# Down_Linker_IM.net
KiCad netlist of a schematic drawn in EAGLE
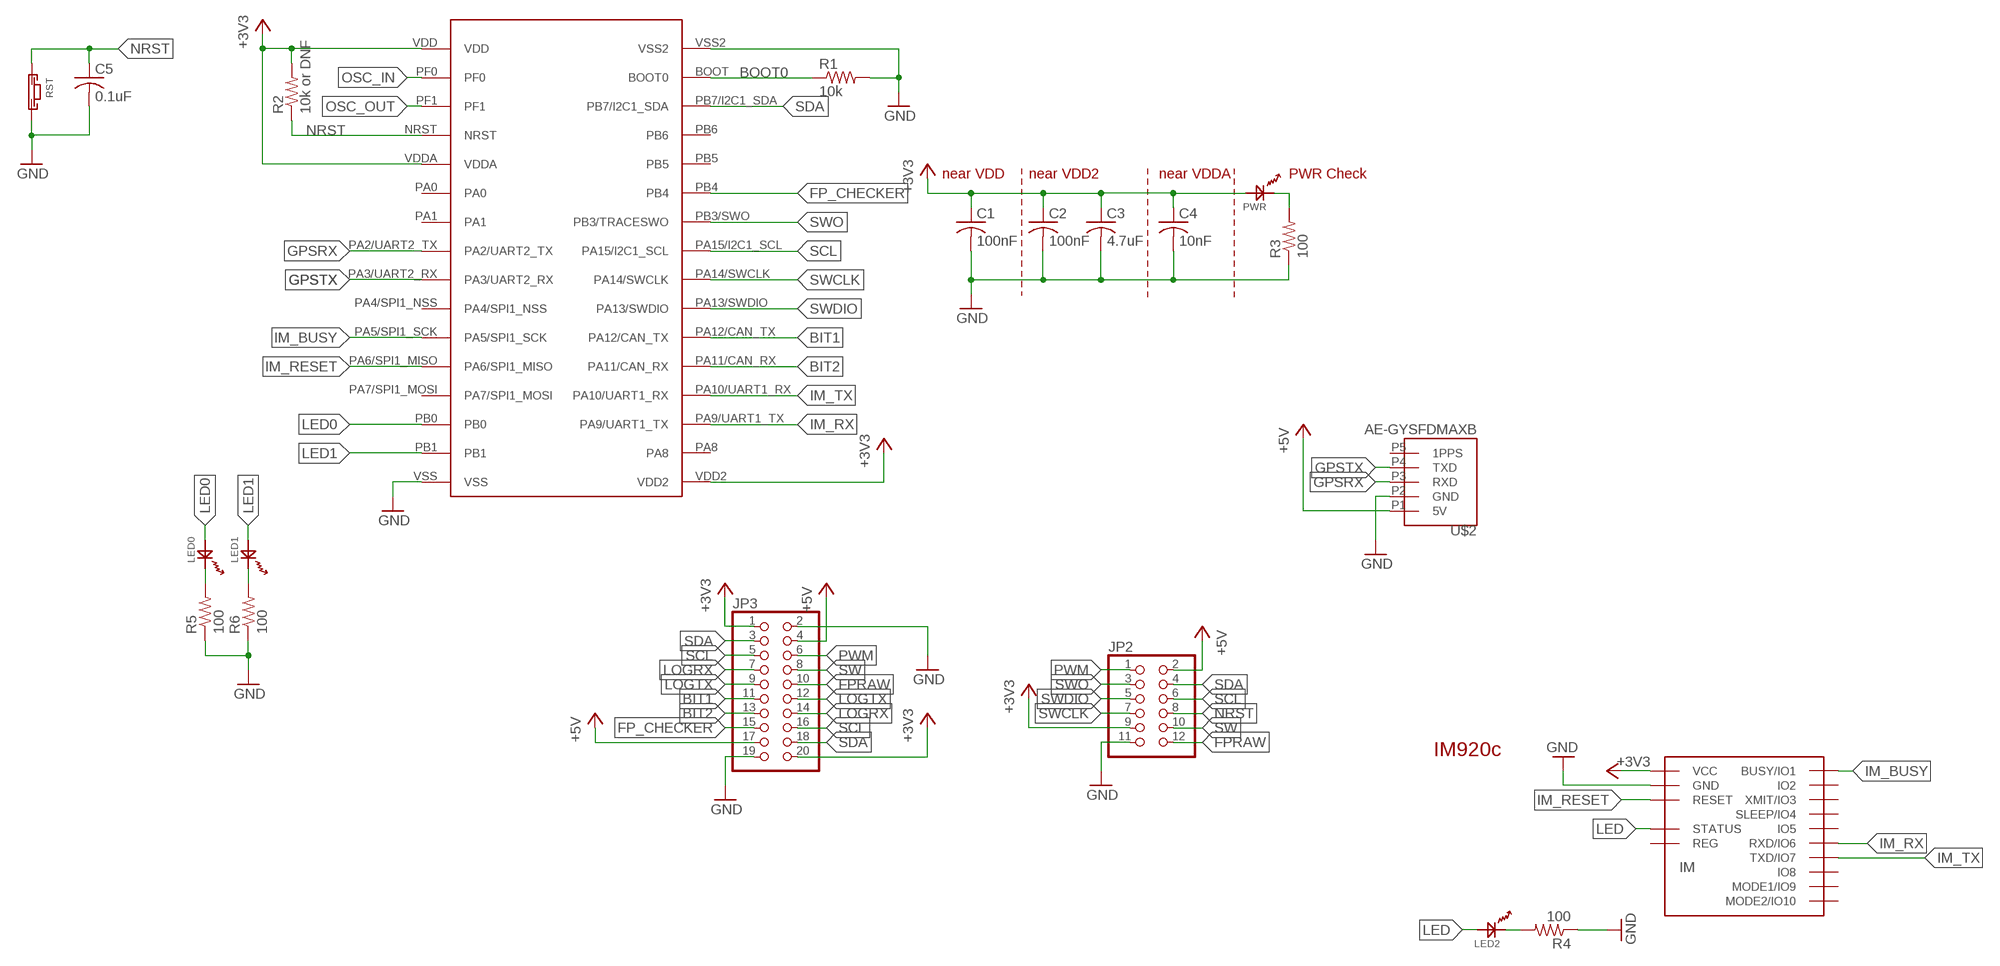
[diagram p0: schematic, sheet 1]

(export (version "E")
  (design (tool "Eeschema 10.0.6"))
  (components
    (comp (ref "C1")
      (value "100nF")
      (footprint "eagle-import:C1608")
      (libsource (lib "eagle-import") (part "C-USC1608"))
    )
    (comp (ref "C2")
      (value "100nF")
      (footprint "eagle-import:C1608")
      (libsource (lib "eagle-import") (part "C-USC1608"))
    )
    (comp (ref "C3")
      (value "4.7uF")
      (footprint "eagle-import:C1608")
      (libsource (lib "eagle-import") (part "C-USC1608"))
    )
    (comp (ref "C4")
      (value "10nF")
      (footprint "eagle-import:C1608")
      (libsource (lib "eagle-import") (part "C-USC1608"))
    )
    (comp (ref "C5")
      (value "0.1uF")
      (footprint "eagle-import:C1608")
      (libsource (lib "eagle-import") (part "C-USC1608"))
    )
    (comp (ref "IM")
      (value "IM920C")
      (footprint "eagle-import:IM920C")
      (libsource (lib "eagle-import") (part "IM920C"))
    )
    (comp (ref "JP2")
      (value "PINHD-2X6/90")
      (footprint "eagle-import:2X06_90")
      (libsource (lib "eagle-import") (part "PINHD-2X6/90"))
    )
    (comp (ref "JP3")
      (value "PINHD-2X10/90")
      (footprint "eagle-import:2X10_90")
      (libsource (lib "eagle-import") (part "PINHD-2X10/90"))
    )
    (comp (ref "LED0")
      (value "OSXX1608C1A")
      (footprint "eagle-import:OSXX1608C1A")
      (libsource (lib "eagle-import") (part "OSXX1608C1A"))
    )
    (comp (ref "LED1")
      (value "OSXX1608C1A")
      (footprint "eagle-import:OSXX1608C1A")
      (libsource (lib "eagle-import") (part "OSXX1608C1A"))
    )
    (comp (ref "LED2")
      (value "OSXX1608C1A")
      (footprint "eagle-import:OSXX1608C1A")
      (libsource (lib "eagle-import") (part "OSXX1608C1A"))
    )
    (comp (ref "PWR")
      (value "OSXX1608C1A")
      (footprint "eagle-import:OSXX1608C1A")
      (libsource (lib "eagle-import") (part "OSXX1608C1A"))
    )
    (comp (ref "R1")
      (value "10k")
      (footprint "eagle-import:R0603")
      (libsource (lib "eagle-import") (part "R-US_R0603"))
    )
    (comp (ref "R2")
      (value "10k or DNF")
      (footprint "eagle-import:R0603")
      (libsource (lib "eagle-import") (part "R-US_R0603"))
    )
    (comp (ref "R3")
      (value "100")
      (footprint "eagle-import:R0603")
      (libsource (lib "eagle-import") (part "R-US_R0603"))
    )
    (comp (ref "R4")
      (value "100")
      (footprint "eagle-import:R0603")
      (libsource (lib "eagle-import") (part "R-US_R0603"))
    )
    (comp (ref "R5")
      (value "100")
      (footprint "eagle-import:R0603")
      (libsource (lib "eagle-import") (part "R-US_R0603"))
    )
    (comp (ref "R6")
      (value "100")
      (footprint "eagle-import:R0603")
      (libsource (lib "eagle-import") (part "R-US_R0603"))
    )
    (comp (ref "RST")
      (value "TVAF06-A020B-R")
      (footprint "eagle-import:TVAF06-A020B-R")
      (libsource (lib "eagle-import") (part "TVAF06-A020B-R"))
    )
    (comp (ref "U$1")
      (value "STM32F303K8")
      (footprint "eagle-import:STM32F303K8")
      (libsource (lib "eagle-import") (part "STM32F303K8"))
    )
    (comp (ref "U$2")
      (value "AE-GYSFDMAXB")
      (footprint "eagle-import:AE-GYSFDMAXB")
      (libsource (lib "eagle-import") (part "AE-GYSFDMAXB"))
    )
  )
  (nets
    (net (code "1") (name "+3V3") (class "Default")
      (node (ref "C1") (pin "1") (pinfunction "1_1") (pintype "passive"))
      (node (ref "C2") (pin "1") (pinfunction "1_1") (pintype "passive"))
      (node (ref "C3") (pin "1") (pinfunction "1_1") (pintype "passive"))
      (node (ref "C4") (pin "1") (pinfunction "1_1") (pintype "passive"))
      (node (ref "IM") (pin "$P17") (pinfunction "VCC_$P17") (pintype "bidirectional"))
      (node (ref "JP2") (pin "9") (pinfunction "9_9") (pintype "passive"))
      (node (ref "JP3") (pin "1") (pinfunction "1_1") (pintype "passive"))
      (node (ref "JP3") (pin "20") (pinfunction "20_20") (pintype "passive"))
      (node (ref "PWR") (pin "AN") (pinfunction "AN_AN") (pintype "bidirectional"))
      (node (ref "R2") (pin "2") (pinfunction "2_2") (pintype "passive"))
      (node (ref "U$1") (pin "VDD") (pinfunction "VDD_VDD") (pintype "power_in"))
      (node (ref "U$1") (pin "VDD2") (pinfunction "VDD2_VDD2") (pintype "power_in"))
      (node (ref "U$1") (pin "VDDA") (pinfunction "VDDA_VDDA") (pintype "power_in"))
    )
    (net (code "2") (name "+5V") (class "Default")
      (node (ref "JP2") (pin "2") (pinfunction "2_2") (pintype "passive"))
      (node (ref "JP3") (pin "17") (pinfunction "17_17") (pintype "passive"))
      (node (ref "JP3") (pin "4") (pinfunction "4_4") (pintype "passive"))
      (node (ref "U$2") (pin "P1") (pinfunction "5V_P1") (pintype "bidirectional"))
    )
    (net (code "3") (name "/BOOT0") (class "Default")
      (node (ref "R1") (pin "1") (pinfunction "1_1") (pintype "passive"))
      (node (ref "U$1") (pin "BOOT") (pinfunction "BOOT0_BOOT") (pintype "bidirectional"))
    )
    (net (code "4") (name "BIT1") (class "Default")
      (node (ref "JP3") (pin "11") (pinfunction "11_11") (pintype "passive"))
      (node (ref "U$1") (pin "PA12/CAN_TX") (pinfunction "PA12/CAN_TX_PA12/CAN_TX") (pintype "bidirectional"))
    )
    (net (code "5") (name "BIT2") (class "Default")
      (node (ref "JP3") (pin "13") (pinfunction "13_13") (pintype "passive"))
      (node (ref "U$1") (pin "PA11/CAN_RX") (pinfunction "PA11/CAN_RX_PA11/CAN_RX") (pintype "bidirectional"))
    )
    (net (code "6") (name "FPRAW") (class "Default")
      (node (ref "JP2") (pin "12") (pinfunction "12_12") (pintype "passive"))
      (node (ref "JP3") (pin "10") (pinfunction "10_10") (pintype "passive"))
    )
    (net (code "7") (name "FP_CHECKER") (class "Default")
      (node (ref "JP3") (pin "15") (pinfunction "15_15") (pintype "passive"))
      (node (ref "U$1") (pin "PB4") (pinfunction "PB4_PB4") (pintype "bidirectional"))
    )
    (net (code "8") (name "GND") (class "Default")
      (node (ref "C1") (pin "2") (pinfunction "2_2") (pintype "passive"))
      (node (ref "C2") (pin "2") (pinfunction "2_2") (pintype "passive"))
      (node (ref "C3") (pin "2") (pinfunction "2_2") (pintype "passive"))
      (node (ref "C4") (pin "2") (pinfunction "2_2") (pintype "passive"))
      (node (ref "C5") (pin "2") (pinfunction "2_2") (pintype "passive"))
      (node (ref "IM") (pin "$P18") (pinfunction "GND_$P18") (pintype "bidirectional"))
      (node (ref "JP2") (pin "11") (pinfunction "11_11") (pintype "passive"))
      (node (ref "JP3") (pin "19") (pinfunction "19_19") (pintype "passive"))
      (node (ref "JP3") (pin "2") (pinfunction "2_2") (pintype "passive"))
      (node (ref "R1") (pin "2") (pinfunction "2_2") (pintype "passive"))
      (node (ref "R3") (pin "1") (pinfunction "1_1") (pintype "passive"))
      (node (ref "R4") (pin "1") (pinfunction "1_1") (pintype "passive"))
      (node (ref "R5") (pin "1") (pinfunction "1_1") (pintype "passive"))
      (node (ref "R6") (pin "1") (pinfunction "1_1") (pintype "passive"))
      (node (ref "RST") (pin "P$2") (pinfunction "P$2_P$2") (pintype "bidirectional"))
      (node (ref "U$1") (pin "VSS") (pinfunction "VSS_VSS") (pintype "power_in"))
      (node (ref "U$1") (pin "VSS2") (pinfunction "VSS2_VSS2") (pintype "power_in"))
      (node (ref "U$2") (pin "P2") (pinfunction "GND_P2") (pintype "bidirectional"))
    )
    (net (code "9") (name "GPSRX") (class "Default")
      (node (ref "U$1") (pin "PA2/UART2_TX") (pinfunction "PA2/UART2_TX_PA2/UART2_TX") (pintype "bidirectional"))
      (node (ref "U$2") (pin "P3") (pinfunction "RXD_P3") (pintype "bidirectional"))
    )
    (net (code "10") (name "GPSTX") (class "Default")
      (node (ref "U$1") (pin "PA3/UART2_RX") (pinfunction "PA3/UART2_RX_PA3/UART2_RX") (pintype "bidirectional"))
      (node (ref "U$2") (pin "P4") (pinfunction "TXD_P4") (pintype "bidirectional"))
    )
    (net (code "11") (name "IM_BUSY") (class "Default")
      (node (ref "IM") (pin "$P1") (pinfunction "BUSY/IO1_$P1") (pintype "bidirectional"))
      (node (ref "U$1") (pin "PA5/SPI1_SCK") (pinfunction "PA5/SPI1_SCK_PA5/SPI1_SCK") (pintype "bidirectional"))
    )
    (net (code "12") (name "IM_RESET") (class "Default")
      (node (ref "IM") (pin "$P19") (pinfunction "RESET_$P19") (pintype "bidirectional"))
      (node (ref "U$1") (pin "PA6/SPI1_MISO") (pinfunction "PA6/SPI1_MISO_PA6/SPI1_MISO") (pintype "bidirectional"))
    )
    (net (code "13") (name "IM_RX") (class "Default")
      (node (ref "IM") (pin "$P6") (pinfunction "RXD/IO6_$P6") (pintype "bidirectional"))
      (node (ref "U$1") (pin "PA9/UART1_TX") (pinfunction "PA9/UART1_TX_PA9/UART1_TX") (pintype "bidirectional"))
    )
    (net (code "14") (name "IM_TX") (class "Default")
      (node (ref "IM") (pin "$P7") (pinfunction "TXD/IO7_$P7") (pintype "bidirectional"))
      (node (ref "U$1") (pin "PA10/UART1_RX") (pinfunction "PA10/UART1_RX_PA10/UART1_RX") (pintype "bidirectional"))
    )
    (net (code "15") (name "LED") (class "Default")
      (node (ref "IM") (pin "$P15") (pinfunction "STATUS_$P15") (pintype "bidirectional"))
      (node (ref "LED2") (pin "AN") (pinfunction "AN_AN") (pintype "bidirectional"))
    )
    (net (code "16") (name "LED0") (class "Default")
      (node (ref "LED0") (pin "AN") (pinfunction "AN_AN") (pintype "bidirectional"))
      (node (ref "U$1") (pin "PB0") (pinfunction "PB0_PB0") (pintype "bidirectional"))
    )
    (net (code "17") (name "LED1") (class "Default")
      (node (ref "LED1") (pin "AN") (pinfunction "AN_AN") (pintype "bidirectional"))
      (node (ref "U$1") (pin "PB1") (pinfunction "PB1_PB1") (pintype "bidirectional"))
    )
    (net (code "18") (name "LOGRX") (class "Default")
      (node (ref "JP3") (pin "14") (pinfunction "14_14") (pintype "passive"))
      (node (ref "JP3") (pin "7") (pinfunction "7_7") (pintype "passive"))
    )
    (net (code "19") (name "LOGTX") (class "Default")
      (node (ref "JP3") (pin "12") (pinfunction "12_12") (pintype "passive"))
      (node (ref "JP3") (pin "9") (pinfunction "9_9") (pintype "passive"))
    )
    (net (code "20") (name "NRST") (class "Default")
      (node (ref "C5") (pin "1") (pinfunction "1_1") (pintype "passive"))
      (node (ref "JP2") (pin "8") (pinfunction "8_8") (pintype "passive"))
      (node (ref "R2") (pin "1") (pinfunction "1_1") (pintype "passive"))
      (node (ref "RST") (pin "P$1") (pinfunction "P$1_P$1") (pintype "bidirectional"))
      (node (ref "U$1") (pin "NRST") (pinfunction "NRST_NRST") (pintype "bidirectional"))
    )
    (net (code "21") (name "Net-(LED0-PadCT)") (class "Default")
      (node (ref "LED0") (pin "CT") (pinfunction "CT_CT") (pintype "bidirectional"))
      (node (ref "R5") (pin "2") (pinfunction "2_2") (pintype "passive"))
    )
    (net (code "22") (name "Net-(LED1-PadCT)") (class "Default")
      (node (ref "LED1") (pin "CT") (pinfunction "CT_CT") (pintype "bidirectional"))
      (node (ref "R6") (pin "2") (pinfunction "2_2") (pintype "passive"))
    )
    (net (code "23") (name "Net-(LED2-PadCT)") (class "Default")
      (node (ref "LED2") (pin "CT") (pinfunction "CT_CT") (pintype "bidirectional"))
      (node (ref "R4") (pin "2") (pinfunction "2_2") (pintype "passive"))
    )
    (net (code "24") (name "Net-(PWR-PadCT)") (class "Default")
      (node (ref "PWR") (pin "CT") (pinfunction "CT_CT") (pintype "bidirectional"))
      (node (ref "R3") (pin "2") (pinfunction "2_2") (pintype "passive"))
    )
    (net (code "25") (name "OSC_IN") (class "Default")
      (node (ref "U$1") (pin "PF0") (pinfunction "PF0_PF0") (pintype "bidirectional"))
    )
    (net (code "26") (name "OSC_OUT") (class "Default")
      (node (ref "U$1") (pin "PF1") (pinfunction "PF1_PF1") (pintype "bidirectional"))
    )
    (net (code "27") (name "PWM") (class "Default")
      (node (ref "JP2") (pin "1") (pinfunction "1_1") (pintype "passive"))
      (node (ref "JP3") (pin "6") (pinfunction "6_6") (pintype "passive"))
    )
    (net (code "28") (name "SCL") (class "Default")
      (node (ref "JP2") (pin "6") (pinfunction "6_6") (pintype "passive"))
      (node (ref "JP3") (pin "16") (pinfunction "16_16") (pintype "passive"))
      (node (ref "JP3") (pin "5") (pinfunction "5_5") (pintype "passive"))
      (node (ref "U$1") (pin "PA15/I2C1_SCL") (pinfunction "PA15/I2C1_SCL_PA15/I2C1_SCL") (pintype "bidirectional"))
    )
    (net (code "29") (name "SDA") (class "Default")
      (node (ref "JP2") (pin "4") (pinfunction "4_4") (pintype "passive"))
      (node (ref "JP3") (pin "18") (pinfunction "18_18") (pintype "passive"))
      (node (ref "JP3") (pin "3") (pinfunction "3_3") (pintype "passive"))
      (node (ref "U$1") (pin "PB7/I2C1_SDA") (pinfunction "PB7/I2C1_SDA_PB7/I2C1_SDA") (pintype "bidirectional"))
    )
    (net (code "30") (name "SW") (class "Default")
      (node (ref "JP2") (pin "10") (pinfunction "10_10") (pintype "passive"))
      (node (ref "JP3") (pin "8") (pinfunction "8_8") (pintype "passive"))
    )
    (net (code "31") (name "SWCLK") (class "Default")
      (node (ref "JP2") (pin "7") (pinfunction "7_7") (pintype "passive"))
      (node (ref "U$1") (pin "PA14/SWCLK") (pinfunction "PA14/SWCLK_PA14/SWCLK") (pintype "bidirectional"))
    )
    (net (code "32") (name "SWDIO") (class "Default")
      (node (ref "JP2") (pin "5") (pinfunction "5_5") (pintype "passive"))
      (node (ref "U$1") (pin "PA13/SWDIO") (pinfunction "PA13/SWDIO_PA13/SWDIO") (pintype "bidirectional"))
    )
    (net (code "33") (name "SWO") (class "Default")
      (node (ref "JP2") (pin "3") (pinfunction "3_3") (pintype "passive"))
      (node (ref "U$1") (pin "PB3/SWO") (pinfunction "PB3/TRACESWO_PB3/SWO") (pintype "bidirectional"))
    )
    (net (code "34") (name "unconnected-(IM-IO2-Pad$P2)") (class "Default")
      (node (ref "IM") (pin "$P2") (pinfunction "IO2_$P2") (pintype "bidirectional"))
    )
    (net (code "35") (name "unconnected-(IM-IO5-Pad$P5)") (class "Default")
      (node (ref "IM") (pin "$P5") (pinfunction "IO5_$P5") (pintype "bidirectional"))
    )
    (net (code "36") (name "unconnected-(IM-IO8-Pad$P8)") (class "Default")
      (node (ref "IM") (pin "$P8") (pinfunction "IO8_$P8") (pintype "bidirectional"))
    )
    (net (code "37") (name "unconnected-(IM-MODE1{slash}IO9-Pad$P9)") (class "Default")
      (node (ref "IM") (pin "$P9") (pinfunction "MODE1/IO9_$P9") (pintype "bidirectional"))
    )
    (net (code "38") (name "unconnected-(IM-MODE2{slash}IO10-Pad$P10)") (class "Default")
      (node (ref "IM") (pin "$P10") (pinfunction "MODE2/IO10_$P10") (pintype "bidirectional"))
    )
    (net (code "39") (name "unconnected-(IM-REG-Pad$P16)") (class "Default")
      (node (ref "IM") (pin "$P16") (pinfunction "REG_$P16") (pintype "bidirectional"))
    )
    (net (code "40") (name "unconnected-(IM-SLEEP{slash}IO4-Pad$P4)") (class "Default")
      (node (ref "IM") (pin "$P4") (pinfunction "SLEEP/IO4_$P4") (pintype "bidirectional"))
    )
    (net (code "41") (name "unconnected-(IM-XMIT{slash}IO3-Pad$P3)") (class "Default")
      (node (ref "IM") (pin "$P3") (pinfunction "XMIT/IO3_$P3") (pintype "bidirectional"))
    )
    (net (code "42") (name "unconnected-(U$1-PadPA0)") (class "Default")
      (node (ref "U$1") (pin "PA0") (pinfunction "PA0_PA0") (pintype "bidirectional"))
    )
    (net (code "43") (name "unconnected-(U$1-PadPA1)") (class "Default")
      (node (ref "U$1") (pin "PA1") (pinfunction "PA1_PA1") (pintype "bidirectional"))
    )
    (net (code "44") (name "unconnected-(U$1-PadPA4{slash}SPI1_NSS)") (class "Default")
      (node (ref "U$1") (pin "PA4/SPI1_NSS") (pinfunction "PA4/SPI1_NSS_PA4/SPI1_NSS") (pintype "bidirectional"))
    )
    (net (code "45") (name "unconnected-(U$1-PadPA7{slash}SPI1_MOSI)") (class "Default")
      (node (ref "U$1") (pin "PA7/SPI1_MOSI") (pinfunction "PA7/SPI1_MOSI_PA7/SPI1_MOSI") (pintype "bidirectional"))
    )
    (net (code "46") (name "unconnected-(U$1-PadPA8)") (class "Default")
      (node (ref "U$1") (pin "PA8") (pinfunction "PA8_PA8") (pintype "bidirectional"))
    )
    (net (code "47") (name "unconnected-(U$1-PadPB5)") (class "Default")
      (node (ref "U$1") (pin "PB5") (pinfunction "PB5_PB5") (pintype "bidirectional"))
    )
    (net (code "48") (name "unconnected-(U$1-PadPB6)") (class "Default")
      (node (ref "U$1") (pin "PB6") (pinfunction "PB6_PB6") (pintype "bidirectional"))
    )
    (net (code "49") (name "unconnected-(U$2-1PPS-PadP5)") (class "Default")
      (node (ref "U$2") (pin "P5") (pinfunction "1PPS_P5") (pintype "bidirectional"))
    )
  )
)
